# Var9.net
KiCad netlist of a schematic drawn in Altium Designer
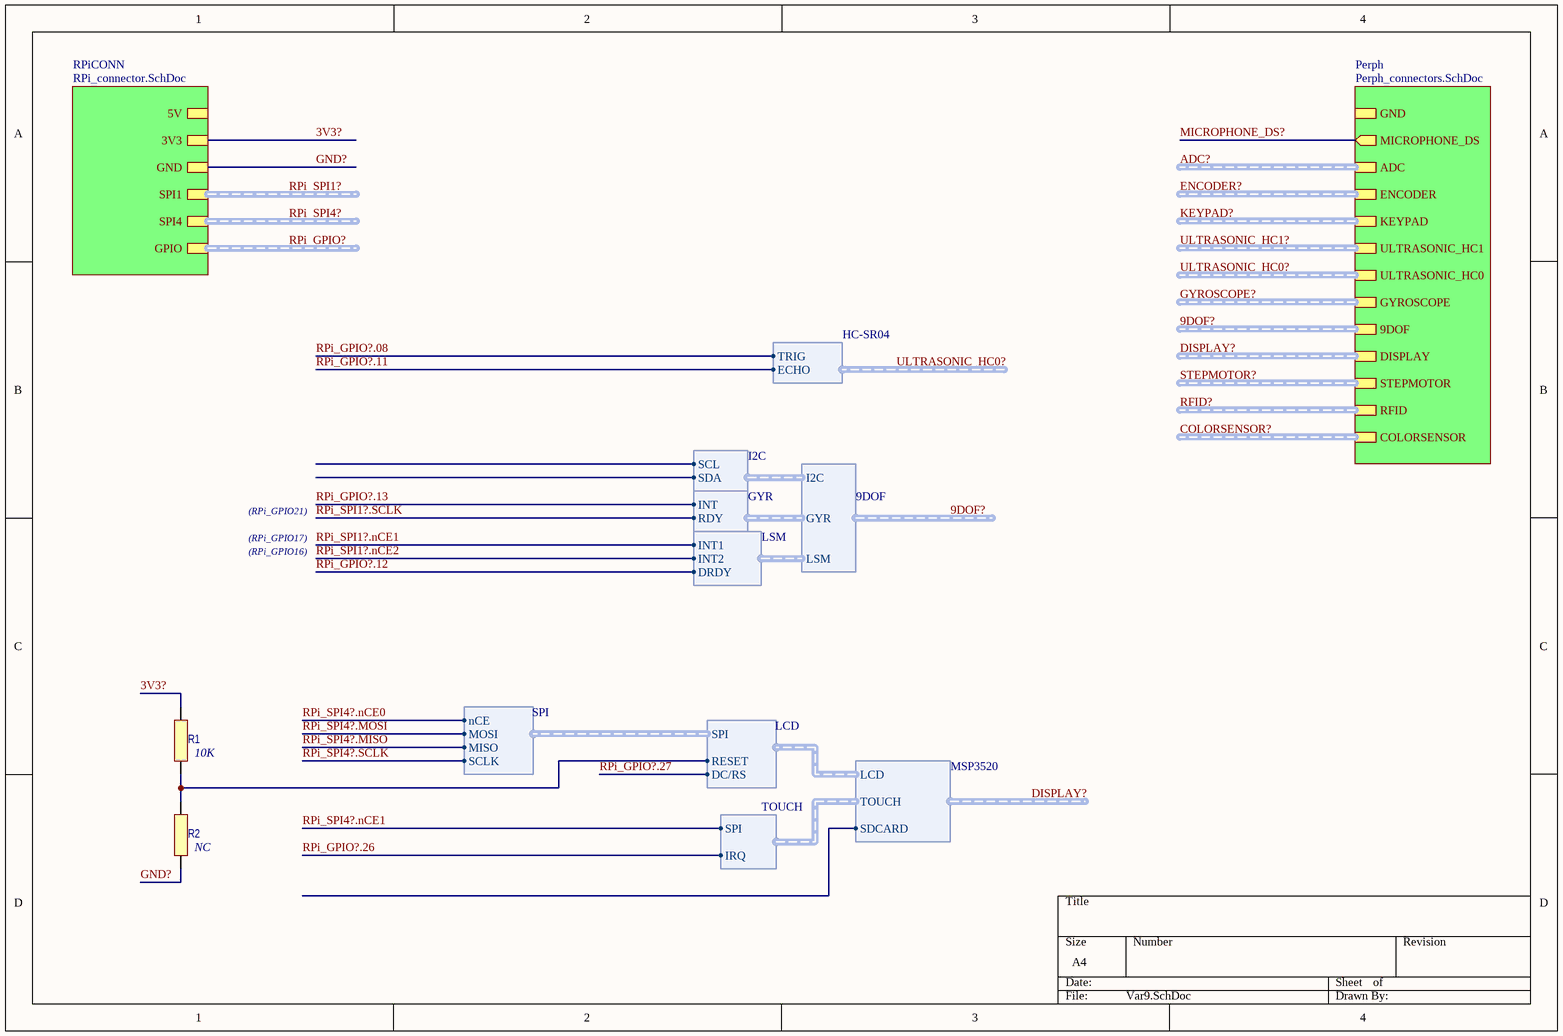
[diagram p0: Var9.SchDoc]

(export (version "E")
  (design (tool "Eeschema 10.0.6"))
  (components
    (comp (ref "R1")
      (value "10K")
      (footprint "R0805")
      (fields (field (name "Comment") "R0805"))
      (libsource (lib "my_AP_lib_sch") (part "R0805"))
    )
    (comp (ref "R2")
      (value "NC")
      (footprint "R0805")
      (fields (field (name "Comment") "R0805"))
      (libsource (lib "my_AP_lib_sch") (part "R0805"))
    )
  )
  (nets
    (net (code "23") (name "/3V3?") (class "Default")
      (node (ref "R1") (pin "1") (pinfunction "1_1") (pintype "passive"))
    )
    (net (code "27") (name "/GND?") (class "Default")
      (node (ref "R2") (pin "2") (pinfunction "2_2") (pintype "passive"))
    )
    (net (code "64") (name "Net-(R1-Pad2)") (class "Default")
      (node (ref "R1") (pin "2") (pinfunction "2_2") (pintype "passive"))
      (node (ref "R2") (pin "1") (pinfunction "1_1") (pintype "passive"))
    )
  )
)
